# HUM-ASM-001.net
KiCad netlist of a schematic drawn in EAGLE
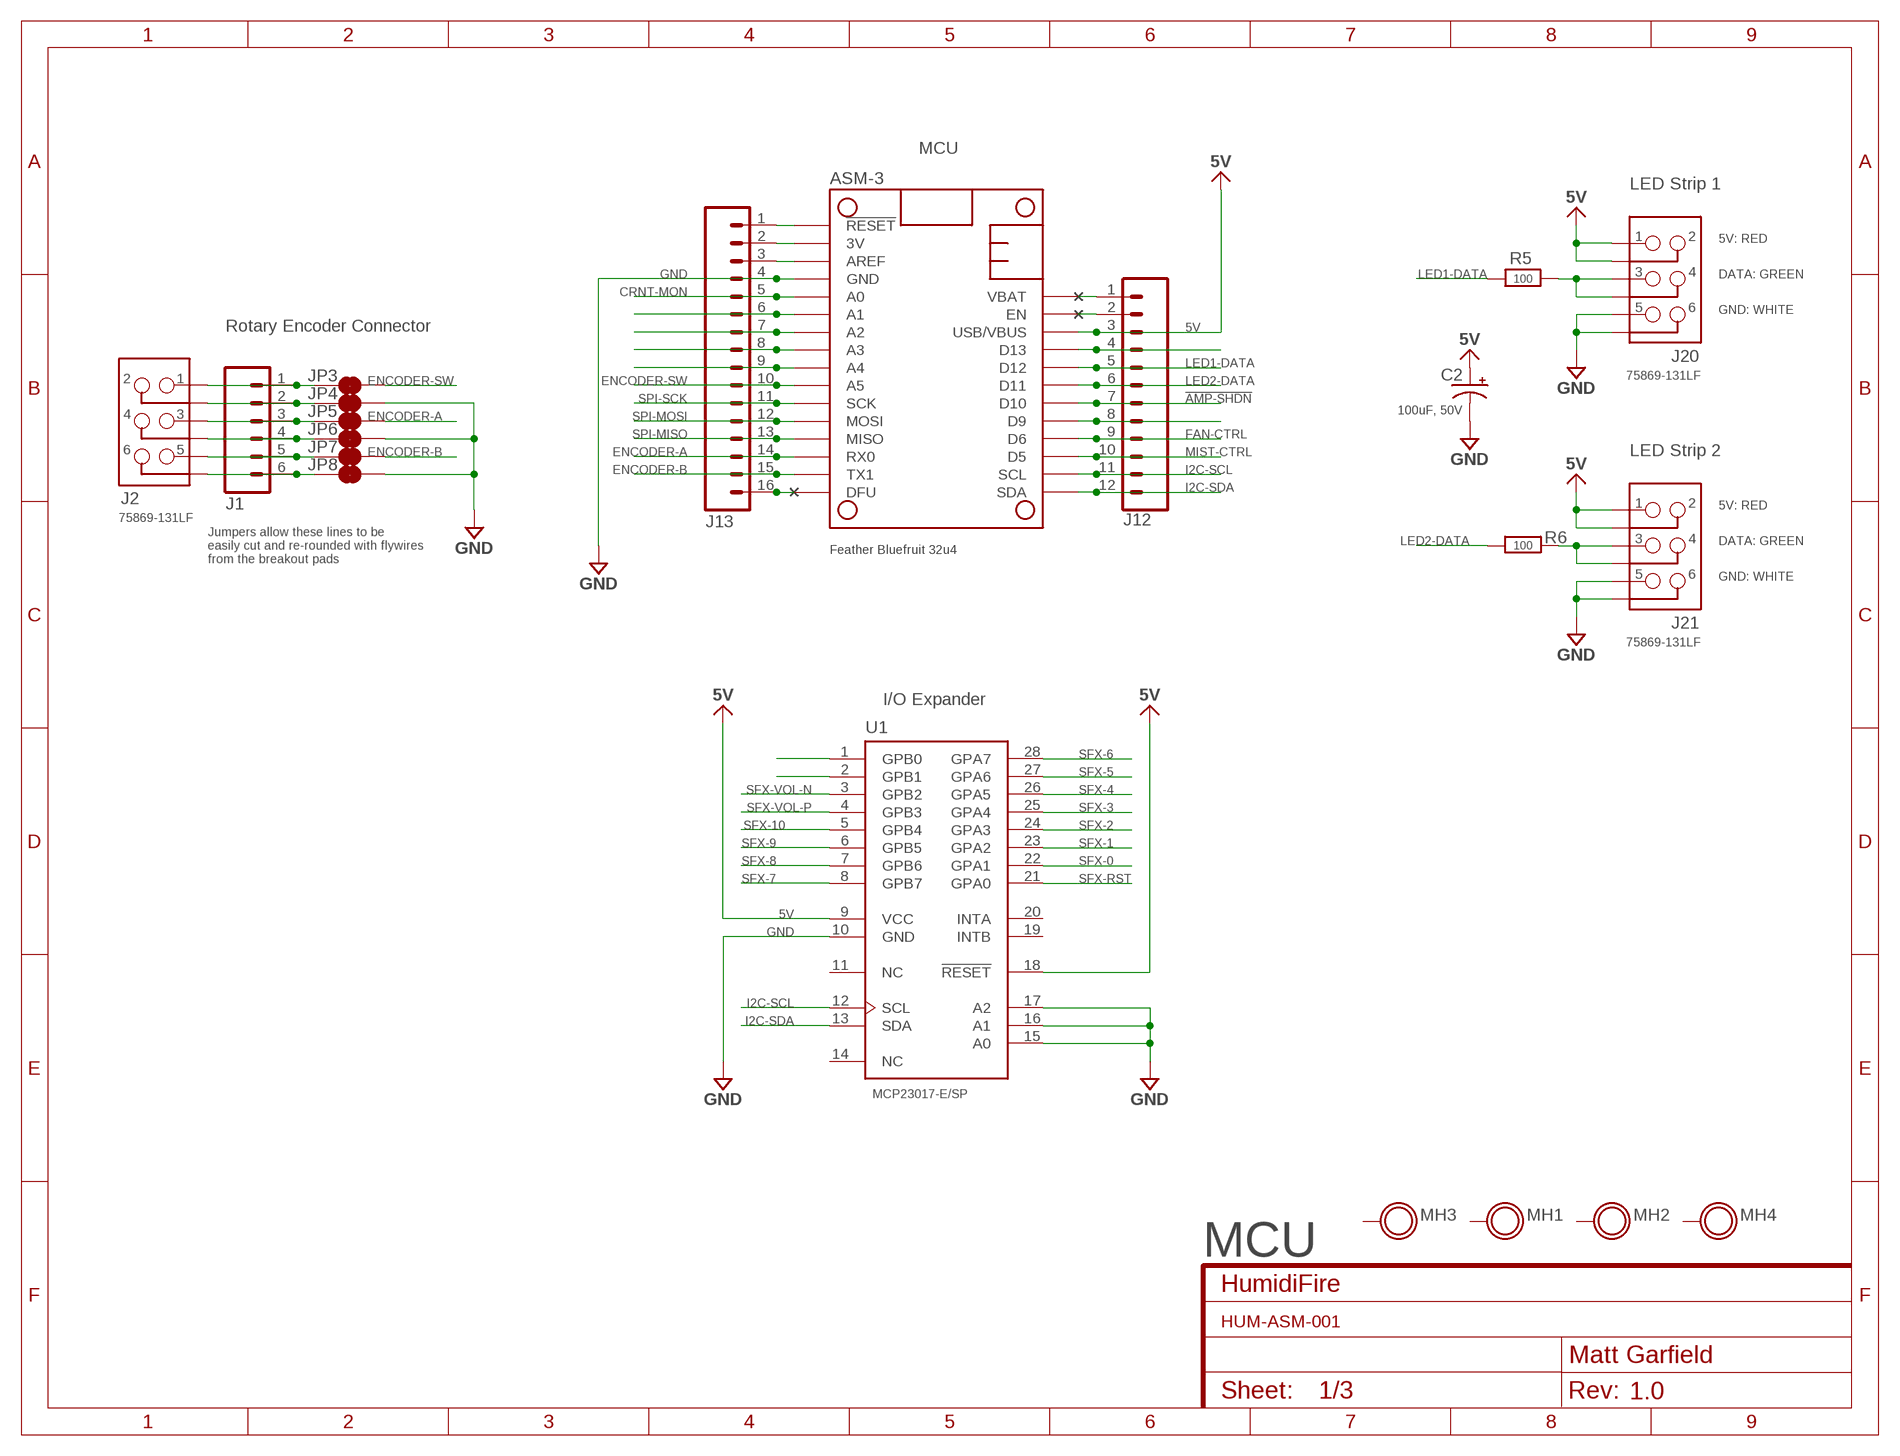
[diagram p0: schematic, sheet 1]
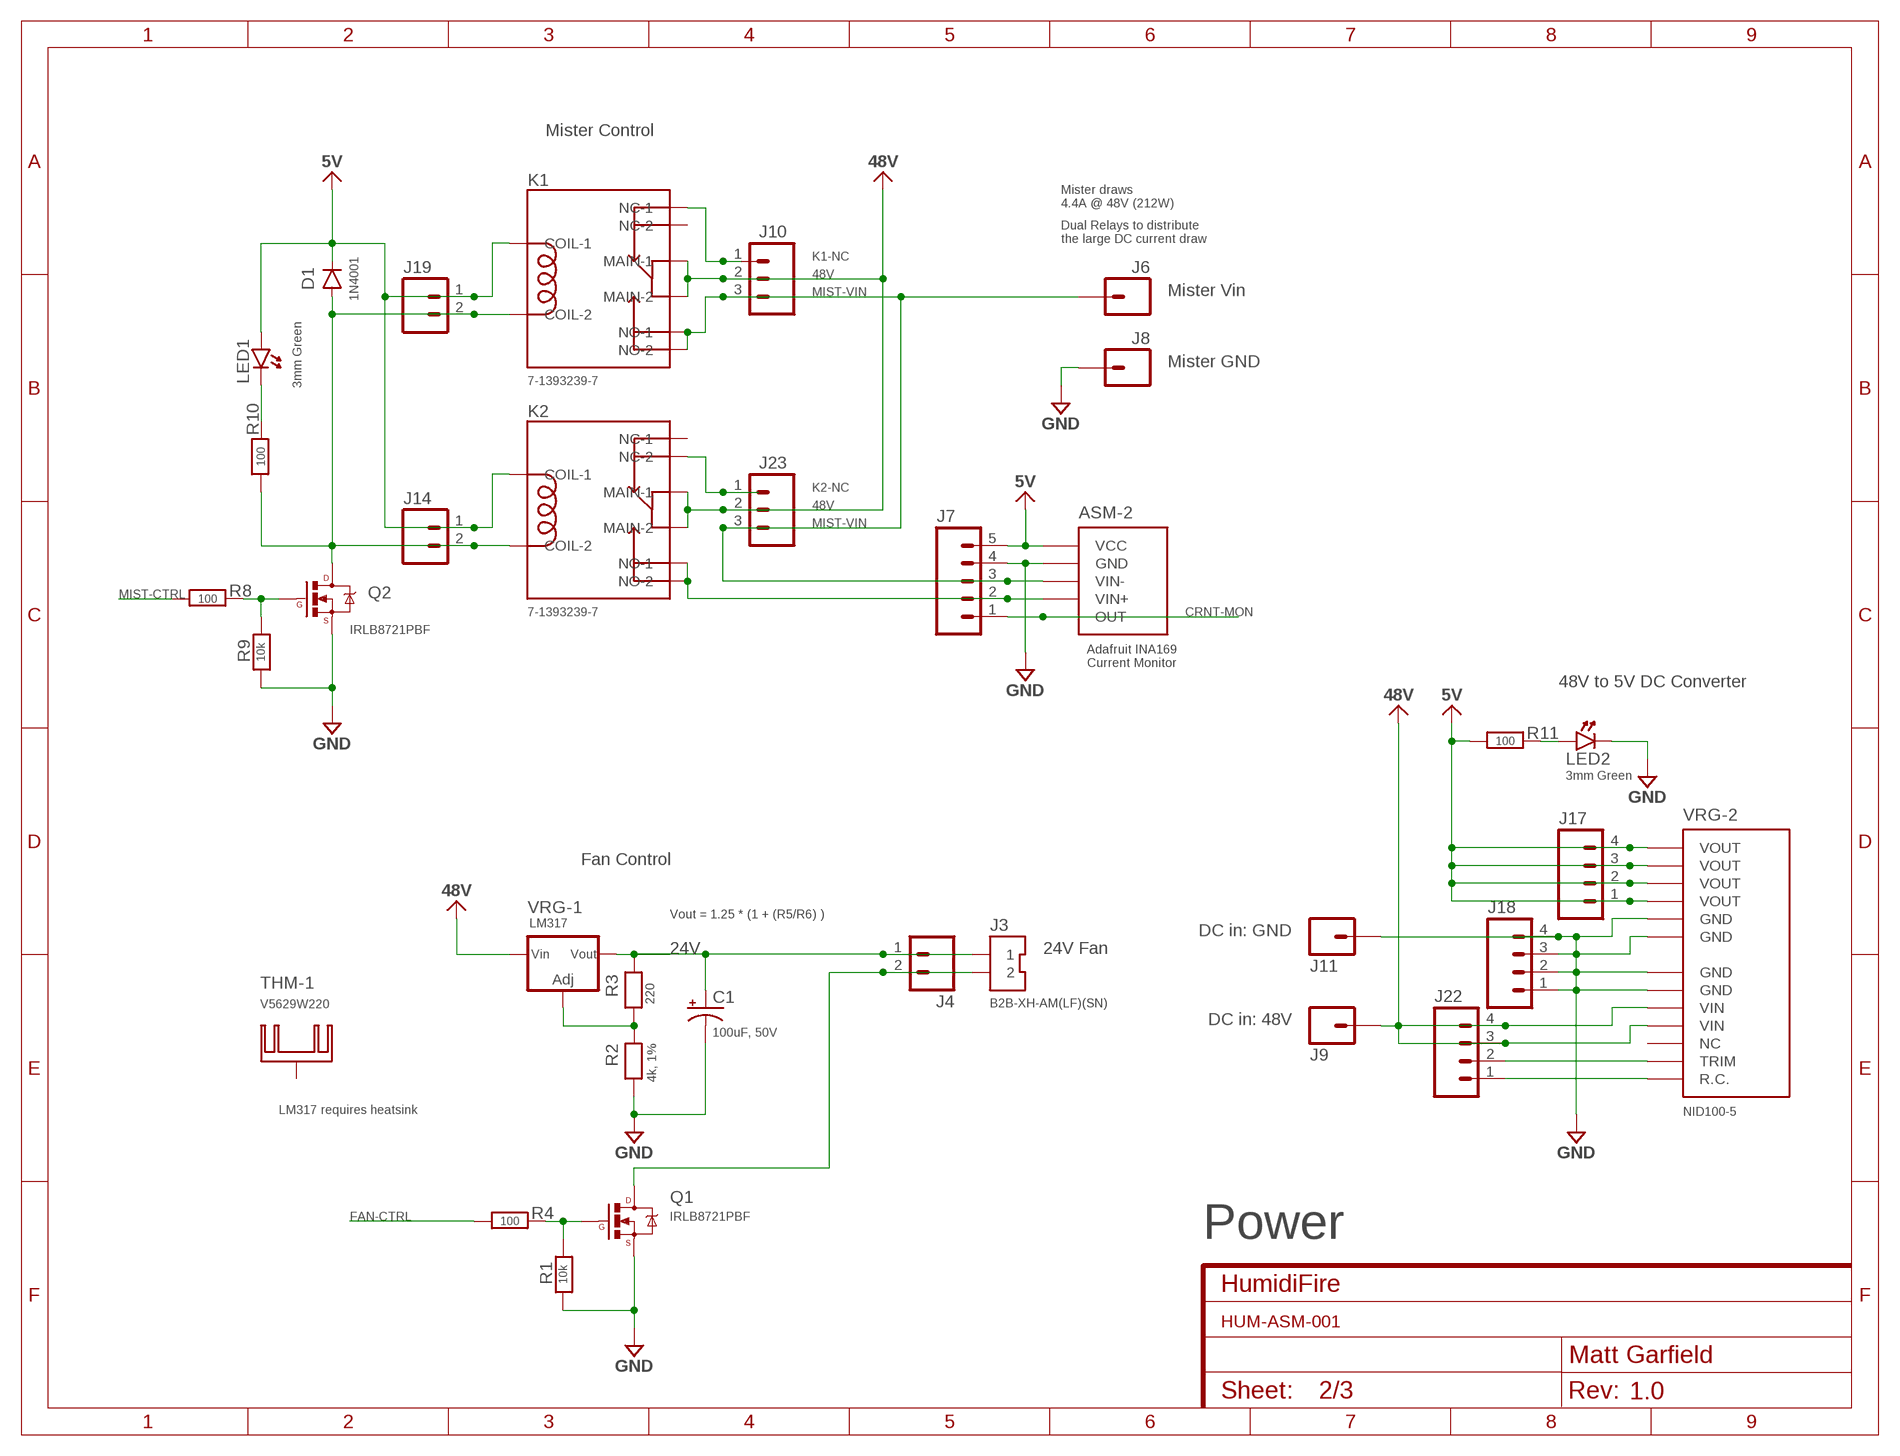
[diagram p1: schematic, sheet 2]
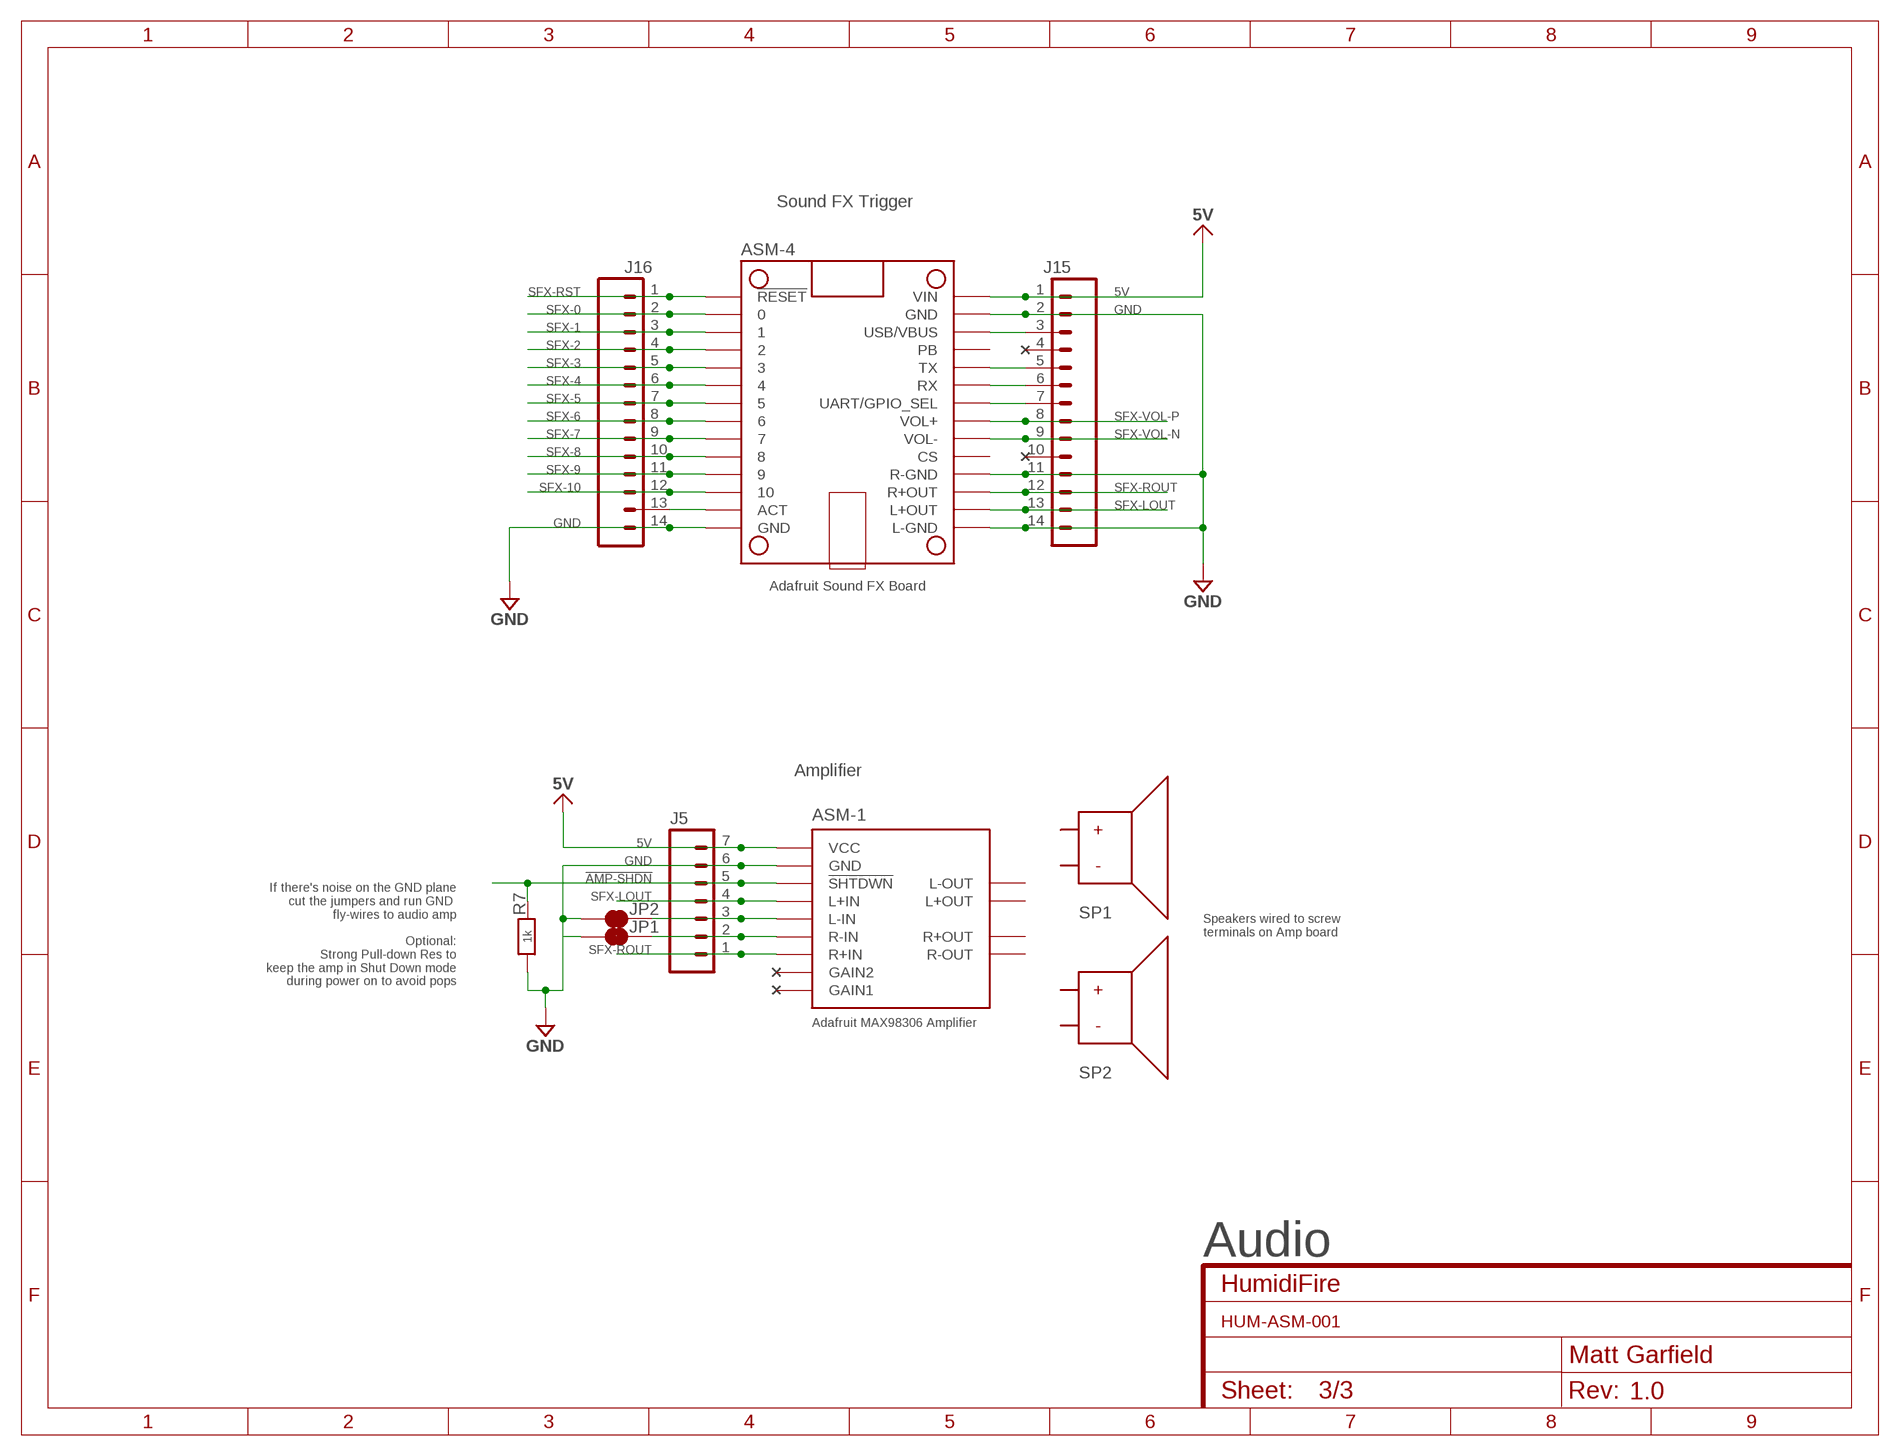
[diagram p2: schematic, sheet 3]

(export (version "E")
  (design (tool "Eeschema 10.0.6"))
  (components
    (comp (ref "ASM-1")
      (value "ASM_ADAFRUIT_MAX98306_AMP")
      (footprint "eagle-import:ASM_ADAFRUIT_MAX98306_AMP_MOUNTING_HOLES")
      (libsource (lib "eagle-import") (part "ASM_ADAFRUIT_MAX98306_AMP"))
    )
    (comp (ref "ASM-4")
      (value "ASM_ADAFRUIT_SOUND_FX_BOARD")
      (footprint "eagle-import:ASM_ADAFRUIT_SOUND_FX_BOARD")
      (libsource (lib "eagle-import") (part "ASM_ADAFRUIT_SOUND_FX_BOARD"))
    )
    (comp (ref "J5")
      (value "CON_HEADER_1X7NO_SILK")
      (footprint "eagle-import:1X07_NO_SILK")
      (libsource (lib "eagle-import") (part "CON_HEADER_1X7NO_SILK"))
    )
    (comp (ref "J15")
      (value "CON_HEADER_1X14")
      (footprint "eagle-import:1X14_NO_SILK")
      (libsource (lib "eagle-import") (part "CON_HEADER_1X14"))
    )
    (comp (ref "J16")
      (value "CON_HEADER_1X14")
      (footprint "eagle-import:1X14_NO_SILK")
      (libsource (lib "eagle-import") (part "CON_HEADER_1X14"))
    )
    (comp (ref "JP1")
      (value "CON_JUMPER_PAD-2-NC_BY_TRACE")
      (footprint "eagle-import:PAD-JUMPER-2-NC_BY_TRACE_YES_SILK")
      (libsource (lib "eagle-import") (part "CON_JUMPER_PAD-2-NC_BY_TRACE"))
    )
    (comp (ref "JP2")
      (value "CON_JUMPER_PAD-2-NC_BY_TRACE")
      (footprint "eagle-import:PAD-JUMPER-2-NC_BY_TRACE_YES_SILK")
      (libsource (lib "eagle-import") (part "CON_JUMPER_PAD-2-NC_BY_TRACE"))
    )
    (comp (ref "R7")
      (value "1k")
      (footprint "eagle-import:AXIAL-0.4")
      (libsource (lib "eagle-import") (part "RES_RESISTOR-PTH-1/4W"))
    )
    (comp (ref "ASM-3")
      (value "Feather Bluefruit 32u4")
      (footprint "eagle-import:ASM_ADAFRUIT_FEATHER_BLUEFRUIT")
      (libsource (lib "eagle-import") (part "ASM_ADAFRUIT_FEATHER_BLUEFRUIT"))
    )
    (comp (ref "C2")
      (value "100uF, 50V")
      (footprint "eagle-import:CAP_E-035X080")
      (libsource (lib "eagle-import") (part "CAP_THT_POL-E-035X080MM"))
    )
    (comp (ref "J1")
      (value "CON_HEADER_1X6NO_SILK_FEMALE_PTH")
      (footprint "eagle-import:1X06_NO_SILK")
      (libsource (lib "eagle-import") (part "CON_HEADER_1X6NO_SILK_FEMALE_PTH"))
    )
    (comp (ref "J2")
      (value "75869-131LF")
      (footprint "eagle-import:2X3-SHROUDED")
      (libsource (lib "eagle-import") (part "CON_HEADER_2X3-SHROUD"))
    )
    (comp (ref "J12")
      (value "CON_HEADER_1X12_NO_SILK")
      (footprint "eagle-import:1X12_NO_SILK")
      (libsource (lib "eagle-import") (part "CON_HEADER_1X12_NO_SILK"))
    )
    (comp (ref "J13")
      (value "CON_HEADER_1X16-1X16_NO_SILK")
      (footprint "eagle-import:1X16_NO_SILK")
      (libsource (lib "eagle-import") (part "CON_HEADER_1X16-1X16_NO_SILK"))
    )
    (comp (ref "J20")
      (value "75869-131LF")
      (footprint "eagle-import:2X3-SHROUDED")
      (libsource (lib "eagle-import") (part "CON_HEADER_2X3-SHROUD"))
    )
    (comp (ref "J21")
      (value "75869-131LF")
      (footprint "eagle-import:2X3-SHROUDED")
      (libsource (lib "eagle-import") (part "CON_HEADER_2X3-SHROUD"))
    )
    (comp (ref "JP3")
      (value "CON_JUMPER_PAD-2-NC_BY_TRACE")
      (footprint "eagle-import:PAD-JUMPER-2-NC_BY_TRACE_YES_SILK")
      (libsource (lib "eagle-import") (part "CON_JUMPER_PAD-2-NC_BY_TRACE"))
    )
    (comp (ref "JP4")
      (value "CON_JUMPER_PAD-2-NC_BY_TRACE")
      (footprint "eagle-import:PAD-JUMPER-2-NC_BY_TRACE_YES_SILK")
      (libsource (lib "eagle-import") (part "CON_JUMPER_PAD-2-NC_BY_TRACE"))
    )
    (comp (ref "JP5")
      (value "CON_JUMPER_PAD-2-NC_BY_TRACE")
      (footprint "eagle-import:PAD-JUMPER-2-NC_BY_TRACE_YES_SILK")
      (libsource (lib "eagle-import") (part "CON_JUMPER_PAD-2-NC_BY_TRACE"))
    )
    (comp (ref "JP6")
      (value "CON_JUMPER_PAD-2-NC_BY_TRACE")
      (footprint "eagle-import:PAD-JUMPER-2-NC_BY_TRACE_YES_SILK")
      (libsource (lib "eagle-import") (part "CON_JUMPER_PAD-2-NC_BY_TRACE"))
    )
    (comp (ref "JP7")
      (value "CON_JUMPER_PAD-2-NC_BY_TRACE")
      (footprint "eagle-import:PAD-JUMPER-2-NC_BY_TRACE_YES_SILK")
      (libsource (lib "eagle-import") (part "CON_JUMPER_PAD-2-NC_BY_TRACE"))
    )
    (comp (ref "JP8")
      (value "CON_JUMPER_PAD-2-NC_BY_TRACE")
      (footprint "eagle-import:PAD-JUMPER-2-NC_BY_TRACE_YES_SILK")
      (libsource (lib "eagle-import") (part "CON_JUMPER_PAD-2-NC_BY_TRACE"))
    )
    (comp (ref "MH1")
      (value "PCB_MOUNTING-HOLE_IN_PLATED")
      (footprint "eagle-import:TOOLING_HOLE_0.125_IN_HORSESHOE")
      (libsource (lib "eagle-import") (part "PCB_MOUNTING-HOLE_IN_PLATED"))
    )
    (comp (ref "MH2")
      (value "PCB_MOUNTING-HOLE_IN_PLATED")
      (footprint "eagle-import:TOOLING_HOLE_0.125_IN_HORSESHOE")
      (libsource (lib "eagle-import") (part "PCB_MOUNTING-HOLE_IN_PLATED"))
    )
    (comp (ref "MH3")
      (value "PCB_MOUNTING-HOLE_IN_PLATED")
      (footprint "eagle-import:TOOLING_HOLE_0.125_IN_HORSESHOE")
      (libsource (lib "eagle-import") (part "PCB_MOUNTING-HOLE_IN_PLATED"))
    )
    (comp (ref "MH4")
      (value "PCB_MOUNTING-HOLE_IN_PLATED")
      (footprint "eagle-import:TOOLING_HOLE_0.125_IN_HORSESHOE")
      (libsource (lib "eagle-import") (part "PCB_MOUNTING-HOLE_IN_PLATED"))
    )
    (comp (ref "R5")
      (value "100")
      (footprint "eagle-import:AXIAL-0.4")
      (libsource (lib "eagle-import") (part "RES_RESISTOR-PTH-1/4W"))
    )
    (comp (ref "R6")
      (value "100")
      (footprint "eagle-import:AXIAL-0.4")
      (libsource (lib "eagle-import") (part "RES_RESISTOR-PTH-1/4W"))
    )
    (comp (ref "U1")
      (value "MCP23017-E/SP")
      (footprint "eagle-import:DIP787W45P254L3556H508Q28")
      (fields (field (name "DIGI-KEY_PART_NUMBER") "MCP23017-E/SP-ND") (field (name "MF") "Microchip"))
      (libsource (lib "eagle-import") (part "IIC_MCP23017-E/SP"))
    )
    (comp (ref "ASM-2")
      (value "ASM_ADAFRUIT_INA169")
      (footprint "eagle-import:ASM_ADAFRUIT_INA169_MOUNTING_HOLES")
      (libsource (lib "eagle-import") (part "ASM_ADAFRUIT_INA169"))
    )
    (comp (ref "C1")
      (value "100uF, 50V")
      (footprint "eagle-import:CAP_E-035X080")
      (libsource (lib "eagle-import") (part "CAP_THT_POL-E-035X080MM"))
    )
    (comp (ref "D1")
      (value "1N4001")
      (footprint "eagle-import:DIODE-1N4001")
      (libsource (lib "eagle-import") (part "DIO_DIODEPTH"))
    )
    (comp (ref "J3")
      (value "B2B-XH-AM(LF)(SN)")
      (footprint "eagle-import:JST-2-PTH-VERT_XH")
      (libsource (lib "eagle-import") (part "CON_JST_2-PIN_B2B-XH-AM"))
    )
    (comp (ref "J4")
      (value "CON_HEADER_1X21X02_NO_SILK")
      (footprint "eagle-import:1X02_NO_SILK")
      (libsource (lib "eagle-import") (part "CON_HEADER_1X21X02_NO_SILK"))
    )
    (comp (ref "J6")
      (value "CON_HEADER_1X1-QC_TAB_121786-1")
      (footprint "eagle-import:TE_1217861-1")
      (libsource (lib "eagle-import") (part "CON_HEADER_1X1-QC_TAB_121786-1"))
    )
    (comp (ref "J7")
      (value "CON_HEADER_1X5NO_SILK")
      (footprint "eagle-import:1X05_NO_SILK")
      (libsource (lib "eagle-import") (part "CON_HEADER_1X5NO_SILK"))
    )
    (comp (ref "J8")
      (value "CON_HEADER_1X1-QC_TAB_121786-1")
      (footprint "eagle-import:TE_1217861-1")
      (libsource (lib "eagle-import") (part "CON_HEADER_1X1-QC_TAB_121786-1"))
    )
    (comp (ref "J9")
      (value "CON_HEADER_1X1-QC_TAB_121786-1")
      (footprint "eagle-import:TE_1217861-1")
      (libsource (lib "eagle-import") (part "CON_HEADER_1X1-QC_TAB_121786-1"))
    )
    (comp (ref "J10")
      (value "CON_HEADER_1X3PTH")
      (footprint "eagle-import:1X03")
      (libsource (lib "eagle-import") (part "CON_HEADER_1X3PTH"))
    )
    (comp (ref "J11")
      (value "CON_HEADER_1X1-QC_TAB_121786-1")
      (footprint "eagle-import:TE_1217861-1")
      (libsource (lib "eagle-import") (part "CON_HEADER_1X1-QC_TAB_121786-1"))
    )
    (comp (ref "J14")
      (value "CON_HEADER_1X21X02_NO_SILK")
      (footprint "eagle-import:1X02_NO_SILK")
      (libsource (lib "eagle-import") (part "CON_HEADER_1X21X02_NO_SILK"))
    )
    (comp (ref "J17")
      (value "CON_HEADER_1X4PTH")
      (footprint "eagle-import:1X04")
      (libsource (lib "eagle-import") (part "CON_HEADER_1X4PTH"))
    )
    (comp (ref "J18")
      (value "CON_HEADER_1X4PTH")
      (footprint "eagle-import:1X04")
      (libsource (lib "eagle-import") (part "CON_HEADER_1X4PTH"))
    )
    (comp (ref "J19")
      (value "CON_HEADER_1X21X02_NO_SILK")
      (footprint "eagle-import:1X02_NO_SILK")
      (libsource (lib "eagle-import") (part "CON_HEADER_1X21X02_NO_SILK"))
    )
    (comp (ref "J22")
      (value "CON_HEADER_1X4NO_SILK_ALL_ROUND")
      (footprint "eagle-import:1X04_NO_SILK_ALL_ROUND")
      (libsource (lib "eagle-import") (part "CON_HEADER_1X4NO_SILK_ALL_ROUND"))
    )
    (comp (ref "J23")
      (value "CON_HEADER_1X3PTH")
      (footprint "eagle-import:1X03")
      (libsource (lib "eagle-import") (part "CON_HEADER_1X3PTH"))
    )
    (comp (ref "K1")
      (value "7-1393239-7")
      (footprint "eagle-import:RELAY_TE_7-1393239-7")
      (libsource (lib "eagle-import") (part "EMD_RELAY_SPDT_8-PIN_TE_7-1393239-7"))
    )
    (comp (ref "K2")
      (value "7-1393239-7")
      (footprint "eagle-import:RELAY_TE_7-1393239-7")
      (libsource (lib "eagle-import") (part "EMD_RELAY_SPDT_8-PIN_TE_7-1393239-7"))
    )
    (comp (ref "LED1")
      (value "3mm Green")
      (footprint "eagle-import:LED3MM")
      (libsource (lib "eagle-import") (part "LED_THT-3MM"))
    )
    (comp (ref "LED2")
      (value "3mm Green")
      (footprint "eagle-import:LED3MM")
      (libsource (lib "eagle-import") (part "LED_THT-3MM"))
    )
    (comp (ref "Q1")
      (value "IRLB8721PBF")
      (footprint "eagle-import:TO-220-VERTICAL")
      (libsource (lib "eagle-import") (part "TRN_MOSFET-N_TO-220_VERTICAL"))
    )
    (comp (ref "Q2")
      (value "IRLB8721PBF")
      (footprint "eagle-import:TO-220-VERTICAL")
      (libsource (lib "eagle-import") (part "TRN_MOSFET-N_TO-220_VERTICAL"))
    )
    (comp (ref "R1")
      (value "10k")
      (footprint "eagle-import:AXIAL-0.4")
      (libsource (lib "eagle-import") (part "RES_RESISTOR-PTH-1/4W"))
    )
    (comp (ref "R2")
      (value "4k, 1%")
      (footprint "eagle-import:AXIAL-0.4")
      (libsource (lib "eagle-import") (part "RES_RESISTOR-PTH-1/4W"))
    )
    (comp (ref "R3")
      (value "220")
      (footprint "eagle-import:AXIAL-0.4")
      (libsource (lib "eagle-import") (part "RES_RESISTOR-PTH-1/4W"))
    )
    (comp (ref "R4")
      (value "100")
      (footprint "eagle-import:AXIAL-0.4")
      (libsource (lib "eagle-import") (part "RES_RESISTOR-PTH-1/4W"))
    )
    (comp (ref "R8")
      (value "100")
      (footprint "eagle-import:AXIAL-0.4")
      (libsource (lib "eagle-import") (part "RES_RESISTOR-PTH-1/4W"))
    )
    (comp (ref "R9")
      (value "10k")
      (footprint "eagle-import:AXIAL-0.4")
      (libsource (lib "eagle-import") (part "RES_RESISTOR-PTH-1/4W"))
    )
    (comp (ref "R10")
      (value "100")
      (footprint "eagle-import:AXIAL-0.4")
      (libsource (lib "eagle-import") (part "RES_RESISTOR-PTH-1/4W"))
    )
    (comp (ref "R11")
      (value "100")
      (footprint "eagle-import:AXIAL-0.4")
      (libsource (lib "eagle-import") (part "RES_RESISTOR-PTH-1/4W"))
    )
    (comp (ref "THM-1")
      (value "V5629W220")
      (footprint "eagle-import:SK95-2M3")
      (libsource (lib "eagle-import") (part "THM_HEATSINK_1-PIN"))
    )
    (comp (ref "VRG-1")
      (value "LM317")
      (footprint "eagle-import:TO-220-VERTICAL")
      (libsource (lib "eagle-import") (part "VRG_LM317_TO-220_VERTICAL"))
    )
    (comp (ref "VRG-2")
      (value "NID100-5")
      (footprint "eagle-import:VRG_NID100-X")
      (libsource (lib "eagle-import") (part "VRG_NID100"))
    )
  )
  (nets
    (net (code "1") (name "5V") (class "Default")
      (node (ref "ASM-1") (pin "1") (pinfunction "VCC_1") (pintype "power_in"))
      (node (ref "ASM-2") (pin "1") (pinfunction "VCC_1") (pintype "power_in"))
      (node (ref "ASM-3") (pin "USB/VBUS") (pinfunction "USB/VBUS_USB/VBUS") (pintype "power_in"))
      (node (ref "ASM-4") (pin "28") (pinfunction "VIN_28") (pintype "power_in"))
      (node (ref "C2") (pin "+") (pinfunction "+_+") (pintype "passive"))
      (node (ref "D1") (pin "C") (pinfunction "C_C") (pintype "passive"))
      (node (ref "J12") (pin "3") (pinfunction "3_3") (pintype "passive"))
      (node (ref "J14") (pin "1") (pinfunction "P1_1") (pintype "passive"))
      (node (ref "J15") (pin "1") (pinfunction "1_1") (pintype "passive"))
      (node (ref "J17") (pin "1") (pinfunction "1_1") (pintype "passive"))
      (node (ref "J17") (pin "2") (pinfunction "2_2") (pintype "passive"))
      (node (ref "J17") (pin "3") (pinfunction "3_3") (pintype "passive"))
      (node (ref "J17") (pin "4") (pinfunction "4_4") (pintype "passive"))
      (node (ref "J19") (pin "1") (pinfunction "P1_1") (pintype "passive"))
      (node (ref "J20") (pin "1") (pinfunction "1_1") (pintype "bidirectional"))
      (node (ref "J20") (pin "2") (pinfunction "2_2") (pintype "bidirectional"))
      (node (ref "J21") (pin "1") (pinfunction "1_1") (pintype "bidirectional"))
      (node (ref "J21") (pin "2") (pinfunction "2_2") (pintype "bidirectional"))
      (node (ref "J5") (pin "7") (pinfunction "7_7") (pintype "passive"))
      (node (ref "J7") (pin "5") (pinfunction "5_5") (pintype "passive"))
      (node (ref "K1") (pin "COIL-1") (pinfunction "COIL-1_COIL-1") (pintype "bidirectional"))
      (node (ref "K2") (pin "COIL-1") (pinfunction "COIL-1_COIL-1") (pintype "bidirectional"))
      (node (ref "LED1") (pin "A") (pinfunction "A_A") (pintype "passive"))
      (node (ref "R11") (pin "P$1") (pinfunction "P1_P$1") (pintype "passive"))
      (node (ref "U1") (pin "18") (pinfunction "~{RESET}_18") (pintype "input"))
      (node (ref "U1") (pin "9") (pinfunction "VCC_9") (pintype "power_in"))
      (node (ref "VRG-2") (pin "P$1") (pinfunction "VOUT_P$1") (pintype "power_in"))
      (node (ref "VRG-2") (pin "P$2") (pinfunction "VOUT_P$2") (pintype "power_in"))
      (node (ref "VRG-2") (pin "P$3") (pinfunction "VOUT_P$3") (pintype "power_in"))
      (node (ref "VRG-2") (pin "P$4") (pinfunction "VOUT_P$4") (pintype "power_in"))
    )
    (net (code "2") (name "24V") (class "Default")
      (node (ref "C1") (pin "+") (pinfunction "+_+") (pintype "passive"))
      (node (ref "J3") (pin "1") (pinfunction "1_1") (pintype "bidirectional"))
      (node (ref "J4") (pin "1") (pinfunction "P1_1") (pintype "passive"))
      (node (ref "R3") (pin "P$2") (pinfunction "P2_P$2") (pintype "passive"))
      (node (ref "VRG-1") (pin "P2") (pinfunction "VOUT_P2") (pintype "power_in"))
    )
    (net (code "3") (name "48V") (class "Default")
      (node (ref "J10") (pin "2") (pinfunction "P2_2") (pintype "passive"))
      (node (ref "J22") (pin "3") (pinfunction "3_3") (pintype "passive"))
      (node (ref "J22") (pin "4") (pinfunction "4_4") (pintype "passive"))
      (node (ref "J23") (pin "2") (pinfunction "P2_2") (pintype "passive"))
      (node (ref "J9") (pin "1") (pinfunction "1_1") (pintype "passive"))
      (node (ref "J9") (pin "2") (pinfunction "1_2") (pintype "passive"))
      (node (ref "K1") (pin "MAIN-1") (pinfunction "MAIN-1_MAIN-1") (pintype "bidirectional"))
      (node (ref "K1") (pin "MAIN-2") (pinfunction "MAIN-2_MAIN-2") (pintype "bidirectional"))
      (node (ref "K2") (pin "MAIN-1") (pinfunction "MAIN-1_MAIN-1") (pintype "bidirectional"))
      (node (ref "K2") (pin "MAIN-2") (pinfunction "MAIN-2_MAIN-2") (pintype "bidirectional"))
      (node (ref "VRG-1") (pin "P3") (pinfunction "VIN_P3") (pintype "power_in"))
      (node (ref "VRG-2") (pin "P$10") (pinfunction "VIN_P$10") (pintype "power_in"))
      (node (ref "VRG-2") (pin "P$9") (pinfunction "VIN_P$9") (pintype "power_in"))
    )
    (net (code "4") (name "CRNT-MON") (class "Default")
      (node (ref "ASM-2") (pin "5") (pinfunction "OUT_5") (pintype "output"))
      (node (ref "ASM-3") (pin "A0") (pinfunction "A0_A0") (pintype "bidirectional"))
      (node (ref "J13") (pin "5") (pinfunction "5_5") (pintype "passive"))
      (node (ref "J7") (pin "1") (pinfunction "1_1") (pintype "passive"))
    )
    (net (code "5") (name "ENCODER-A") (class "Default")
      (node (ref "ASM-3") (pin "RX0") (pinfunction "RX0_RX0") (pintype "bidirectional"))
      (node (ref "J13") (pin "14") (pinfunction "14_14") (pintype "passive"))
      (node (ref "JP5") (pin "1") (pinfunction "1_1") (pintype "passive"))
    )
    (net (code "6") (name "ENCODER-B") (class "Default")
      (node (ref "ASM-3") (pin "TX1") (pinfunction "TX1_TX1") (pintype "bidirectional"))
      (node (ref "J13") (pin "15") (pinfunction "15_15") (pintype "passive"))
      (node (ref "JP7") (pin "1") (pinfunction "1_1") (pintype "passive"))
    )
    (net (code "7") (name "ENCODER-SW") (class "Default")
      (node (ref "ASM-3") (pin "A5") (pinfunction "A5_A5") (pintype "bidirectional"))
      (node (ref "J13") (pin "10") (pinfunction "10_10") (pintype "passive"))
      (node (ref "JP3") (pin "1") (pinfunction "1_1") (pintype "passive"))
    )
    (net (code "8") (name "FAN-CTRL") (class "Default")
      (node (ref "ASM-3") (pin "D6") (pinfunction "D6_D6") (pintype "bidirectional"))
      (node (ref "J12") (pin "9") (pinfunction "9_9") (pintype "passive"))
      (node (ref "R4") (pin "P$1") (pinfunction "P1_P$1") (pintype "passive"))
    )
    (net (code "9") (name "GND") (class "Default")
      (node (ref "ASM-1") (pin "2") (pinfunction "GND_2") (pintype "power_in"))
      (node (ref "ASM-2") (pin "2") (pinfunction "GND_2") (pintype "power_in"))
      (node (ref "ASM-3") (pin "GND@4") (pinfunction "GND_GND@4") (pintype "power_in"))
      (node (ref "ASM-4") (pin "14") (pinfunction "GND_14") (pintype "power_in"))
      (node (ref "ASM-4") (pin "15") (pinfunction "L-GND_15") (pintype "power_in"))
      (node (ref "ASM-4") (pin "18") (pinfunction "R-GND_18") (pintype "bidirectional"))
      (node (ref "ASM-4") (pin "27") (pinfunction "GND_27") (pintype "power_in"))
      (node (ref "C1") (pin "-") (pinfunction "-_-") (pintype "passive"))
      (node (ref "C2") (pin "-") (pinfunction "-_-") (pintype "passive"))
      (node (ref "J11") (pin "1") (pinfunction "1_1") (pintype "passive"))
      (node (ref "J11") (pin "2") (pinfunction "1_2") (pintype "passive"))
      (node (ref "J13") (pin "4") (pinfunction "4_4") (pintype "passive"))
      (node (ref "J15") (pin "11") (pinfunction "11_11") (pintype "passive"))
      (node (ref "J15") (pin "14") (pinfunction "14_14") (pintype "passive"))
      (node (ref "J15") (pin "2") (pinfunction "2_2") (pintype "passive"))
      (node (ref "J16") (pin "14") (pinfunction "14_14") (pintype "passive"))
      (node (ref "J18") (pin "1") (pinfunction "1_1") (pintype "passive"))
      (node (ref "J18") (pin "2") (pinfunction "2_2") (pintype "passive"))
      (node (ref "J18") (pin "3") (pinfunction "3_3") (pintype "passive"))
      (node (ref "J18") (pin "4") (pinfunction "4_4") (pintype "passive"))
      (node (ref "J20") (pin "5") (pinfunction "5_5") (pintype "bidirectional"))
      (node (ref "J20") (pin "6") (pinfunction "6_6") (pintype "bidirectional"))
      (node (ref "J21") (pin "5") (pinfunction "5_5") (pintype "bidirectional"))
      (node (ref "J21") (pin "6") (pinfunction "6_6") (pintype "bidirectional"))
      (node (ref "J5") (pin "6") (pinfunction "6_6") (pintype "passive"))
      (node (ref "J7") (pin "4") (pinfunction "4_4") (pintype "passive"))
      (node (ref "J8") (pin "1") (pinfunction "1_1") (pintype "passive"))
      (node (ref "J8") (pin "2") (pinfunction "1_2") (pintype "passive"))
      (node (ref "JP1") (pin "1") (pinfunction "1_1") (pintype "passive"))
      (node (ref "JP2") (pin "1") (pinfunction "1_1") (pintype "passive"))
      (node (ref "JP4") (pin "1") (pinfunction "1_1") (pintype "passive"))
      (node (ref "JP6") (pin "1") (pinfunction "1_1") (pintype "passive"))
      (node (ref "JP8") (pin "1") (pinfunction "1_1") (pintype "passive"))
      (node (ref "LED2") (pin "K") (pinfunction "C_K") (pintype "passive"))
      (node (ref "Q1") (pin "P3") (pinfunction "S_P3") (pintype "passive"))
      (node (ref "Q2") (pin "P3") (pinfunction "S_P3") (pintype "passive"))
      (node (ref "R1") (pin "P$2") (pinfunction "P2_P$2") (pintype "passive"))
      (node (ref "R2") (pin "P$1") (pinfunction "P1_P$1") (pintype "passive"))
      (node (ref "R7") (pin "P$1") (pinfunction "P1_P$1") (pintype "passive"))
      (node (ref "R9") (pin "P$2") (pinfunction "P2_P$2") (pintype "passive"))
      (node (ref "U1") (pin "10") (pinfunction "GND_10") (pintype "power_in"))
      (node (ref "U1") (pin "15") (pinfunction "A0_15") (pintype "input"))
      (node (ref "U1") (pin "16") (pinfunction "A1_16") (pintype "input"))
      (node (ref "U1") (pin "17") (pinfunction "A2_17") (pintype "input"))
      (node (ref "VRG-2") (pin "P$5") (pinfunction "GND_P$5") (pintype "power_in"))
      (node (ref "VRG-2") (pin "P$6") (pinfunction "GND_P$6") (pintype "power_in"))
      (node (ref "VRG-2") (pin "P$7") (pinfunction "GND_P$7") (pintype "power_in"))
      (node (ref "VRG-2") (pin "P$8") (pinfunction "GND_P$8") (pintype "power_in"))
    )
    (net (code "10") (name "I2C-SCL") (class "Default")
      (node (ref "ASM-3") (pin "SCL") (pinfunction "SCL_SCL") (pintype "bidirectional"))
      (node (ref "J12") (pin "11") (pinfunction "11_11") (pintype "passive"))
      (node (ref "U1") (pin "12") (pinfunction "SCL_12") (pintype "input"))
    )
    (net (code "11") (name "I2C-SDA") (class "Default")
      (node (ref "ASM-3") (pin "SDA") (pinfunction "SDA_SDA") (pintype "bidirectional"))
      (node (ref "J12") (pin "12") (pinfunction "12_12") (pintype "passive"))
      (node (ref "U1") (pin "13") (pinfunction "SDA_13") (pintype "bidirectional"))
    )
    (net (code "12") (name "K1-NC") (class "Default")
      (node (ref "J10") (pin "1") (pinfunction "P1_1") (pintype "passive"))
      (node (ref "K1") (pin "NC-1") (pinfunction "NC-1_NC-1") (pintype "bidirectional"))
    )
    (net (code "13") (name "K2-NC") (class "Default")
      (node (ref "J23") (pin "1") (pinfunction "P1_1") (pintype "passive"))
      (node (ref "K2") (pin "NC-2") (pinfunction "NC-2_NC-2") (pintype "bidirectional"))
    )
    (net (code "14") (name "LED1-DATA") (class "Default")
      (node (ref "ASM-3") (pin "D12") (pinfunction "D12_D12") (pintype "bidirectional"))
      (node (ref "J12") (pin "5") (pinfunction "5_5") (pintype "passive"))
      (node (ref "R5") (pin "P$2") (pinfunction "P2_P$2") (pintype "passive"))
    )
    (net (code "15") (name "LED2-DATA") (class "Default")
      (node (ref "ASM-3") (pin "D11") (pinfunction "D11_D11") (pintype "bidirectional"))
      (node (ref "J12") (pin "6") (pinfunction "6_6") (pintype "passive"))
      (node (ref "R6") (pin "P$1") (pinfunction "P1_P$1") (pintype "passive"))
    )
    (net (code "16") (name "MIST-CTRL") (class "Default")
      (node (ref "ASM-3") (pin "D5") (pinfunction "D5_D5") (pintype "bidirectional"))
      (node (ref "J12") (pin "10") (pinfunction "10_10") (pintype "passive"))
      (node (ref "R8") (pin "P$1") (pinfunction "P1_P$1") (pintype "passive"))
    )
    (net (code "17") (name "MIST-VIN") (class "Default")
      (node (ref "ASM-2") (pin "3") (pinfunction "VIN-_3") (pintype "bidirectional"))
      (node (ref "J10") (pin "3") (pinfunction "P3_3") (pintype "passive"))
      (node (ref "J23") (pin "3") (pinfunction "P3_3") (pintype "passive"))
      (node (ref "J6") (pin "1") (pinfunction "1_1") (pintype "passive"))
      (node (ref "J6") (pin "2") (pinfunction "1_2") (pintype "passive"))
      (node (ref "J7") (pin "3") (pinfunction "3_3") (pintype "passive"))
      (node (ref "K1") (pin "NO-1") (pinfunction "NO-1_NO-1") (pintype "bidirectional"))
      (node (ref "K1") (pin "NO-2") (pinfunction "NO-2_NO-2") (pintype "bidirectional"))
    )
    (net (code "18") (name "Net-(ASM-1-L-IN)") (class "Default")
      (node (ref "ASM-1") (pin "5") (pinfunction "L-IN_5") (pintype "input"))
      (node (ref "J5") (pin "3") (pinfunction "3_3") (pintype "passive"))
      (node (ref "JP2") (pin "2") (pinfunction "2_2") (pintype "passive"))
    )
    (net (code "19") (name "Net-(ASM-1-R-IN)") (class "Default")
      (node (ref "ASM-1") (pin "6") (pinfunction "R-IN_6") (pintype "input"))
      (node (ref "J5") (pin "2") (pinfunction "2_2") (pintype "passive"))
      (node (ref "JP1") (pin "2") (pinfunction "2_2") (pintype "passive"))
    )
    (net (code "20") (name "Net-(ASM-2-VIN+)") (class "Default")
      (node (ref "ASM-2") (pin "4") (pinfunction "VIN+_4") (pintype "bidirectional"))
      (node (ref "J7") (pin "2") (pinfunction "2_2") (pintype "passive"))
      (node (ref "K2") (pin "NO-1") (pinfunction "NO-1_NO-1") (pintype "bidirectional"))
      (node (ref "K2") (pin "NO-2") (pinfunction "NO-2_NO-2") (pintype "bidirectional"))
    )
    (net (code "21") (name "Net-(ASM-3-3V)") (class "Default")
      (node (ref "ASM-3") (pin "3V3") (pinfunction "3V_3V3") (pintype "power_in"))
      (node (ref "J13") (pin "2") (pinfunction "2_2") (pintype "passive"))
    )
    (net (code "22") (name "Net-(ASM-3-PadA1)") (class "Default")
      (node (ref "ASM-3") (pin "A1") (pinfunction "A1_A1") (pintype "bidirectional"))
      (node (ref "J13") (pin "6") (pinfunction "6_6") (pintype "passive"))
    )
    (net (code "23") (name "Net-(ASM-3-PadA2)") (class "Default")
      (node (ref "ASM-3") (pin "A2") (pinfunction "A2_A2") (pintype "bidirectional"))
      (node (ref "J13") (pin "7") (pinfunction "7_7") (pintype "passive"))
    )
    (net (code "24") (name "Net-(ASM-3-PadA3)") (class "Default")
      (node (ref "ASM-3") (pin "A3") (pinfunction "A3_A3") (pintype "bidirectional"))
      (node (ref "J13") (pin "8") (pinfunction "8_8") (pintype "passive"))
    )
    (net (code "25") (name "Net-(ASM-3-PadA4)") (class "Default")
      (node (ref "ASM-3") (pin "A4") (pinfunction "A4_A4") (pintype "bidirectional"))
      (node (ref "J13") (pin "9") (pinfunction "9_9") (pintype "passive"))
    )
    (net (code "26") (name "Net-(ASM-3-PadAREF)") (class "Default")
      (node (ref "ASM-3") (pin "AREF") (pinfunction "AREF_AREF") (pintype "passive"))
      (node (ref "J13") (pin "3") (pinfunction "3_3") (pintype "passive"))
    )
    (net (code "27") (name "Net-(ASM-3-PadD9)") (class "Default")
      (node (ref "ASM-3") (pin "D9") (pinfunction "D9_D9") (pintype "bidirectional"))
      (node (ref "J12") (pin "8") (pinfunction "8_8") (pintype "passive"))
    )
    (net (code "28") (name "Net-(ASM-3-PadD13)") (class "Default")
      (node (ref "ASM-3") (pin "D13") (pinfunction "D13_D13") (pintype "bidirectional"))
      (node (ref "J12") (pin "4") (pinfunction "4_4") (pintype "passive"))
    )
    (net (code "29") (name "Net-(ASM-3-PadDFU)") (class "Default")
      (node (ref "ASM-3") (pin "DFU") (pinfunction "DFU_DFU") (pintype "bidirectional"))
      (node (ref "J13") (pin "16") (pinfunction "16_16") (pintype "passive"))
    )
    (net (code "30") (name "Net-(ASM-3-PadEN)") (class "Default")
      (node (ref "ASM-3") (pin "EN") (pinfunction "EN_EN") (pintype "passive"))
      (node (ref "J12") (pin "2") (pinfunction "2_2") (pintype "passive"))
    )
    (net (code "31") (name "Net-(ASM-3-PadVBAT)") (class "Default")
      (node (ref "ASM-3") (pin "VBAT") (pinfunction "VBAT_VBAT") (pintype "power_in"))
      (node (ref "J12") (pin "1") (pinfunction "1_1") (pintype "passive"))
    )
    (net (code "32") (name "Net-(ASM-3-~{RESET})") (class "Default")
      (node (ref "ASM-3") (pin "!RESET") (pinfunction "~{RESET}_!RESET") (pintype "input"))
      (node (ref "J13") (pin "1") (pinfunction "1_1") (pintype "passive"))
    )
    (net (code "33") (name "Net-(ASM-4-ACT)") (class "Default")
      (node (ref "ASM-4") (pin "13") (pinfunction "ACT_13") (pintype "output"))
      (node (ref "J16") (pin "13") (pinfunction "13_13") (pintype "passive"))
    )
    (net (code "34") (name "Net-(ASM-4-RX)") (class "Default")
      (node (ref "ASM-4") (pin "23") (pinfunction "RX_23") (pintype "input"))
      (node (ref "J15") (pin "6") (pinfunction "6_6") (pintype "passive"))
    )
    (net (code "35") (name "Net-(ASM-4-TX)") (class "Default")
      (node (ref "ASM-4") (pin "24") (pinfunction "TX_24") (pintype "output"))
      (node (ref "J15") (pin "5") (pinfunction "5_5") (pintype "passive"))
    )
    (net (code "36") (name "Net-(ASM-4-UART{slash}GPIO_SEL)") (class "Default")
      (node (ref "ASM-4") (pin "22") (pinfunction "UART/GPIO_SEL_22") (pintype "bidirectional"))
      (node (ref "J15") (pin "7") (pinfunction "7_7") (pintype "passive"))
    )
    (net (code "37") (name "Net-(ASM-4-USB{slash}VBUS)") (class "Default")
      (node (ref "ASM-4") (pin "26") (pinfunction "USB/VBUS_26") (pintype "power_in"))
      (node (ref "J15") (pin "3") (pinfunction "3_3") (pintype "passive"))
    )
    (net (code "38") (name "Net-(J1-Pad1)") (class "Default")
      (node (ref "J1") (pin "1") (pinfunction "1_1") (pintype "passive"))
      (node (ref "J2") (pin "1") (pinfunction "1_1") (pintype "bidirectional"))
      (node (ref "JP3") (pin "2") (pinfunction "2_2") (pintype "passive"))
    )
    (net (code "39") (name "Net-(J1-Pad2)") (class "Default")
      (node (ref "J1") (pin "2") (pinfunction "2_2") (pintype "passive"))
      (node (ref "J2") (pin "2") (pinfunction "2_2") (pintype "bidirectional"))
      (node (ref "JP4") (pin "2") (pinfunction "2_2") (pintype "passive"))
    )
    (net (code "40") (name "Net-(J1-Pad3)") (class "Default")
      (node (ref "J1") (pin "3") (pinfunction "3_3") (pintype "passive"))
      (node (ref "J2") (pin "3") (pinfunction "3_3") (pintype "bidirectional"))
      (node (ref "JP5") (pin "2") (pinfunction "2_2") (pintype "passive"))
    )
    (net (code "41") (name "Net-(J1-Pad4)") (class "Default")
      (node (ref "J1") (pin "4") (pinfunction "4_4") (pintype "passive"))
      (node (ref "J2") (pin "4") (pinfunction "4_4") (pintype "bidirectional"))
      (node (ref "JP6") (pin "2") (pinfunction "2_2") (pintype "passive"))
    )
    (net (code "42") (name "Net-(J1-Pad5)") (class "Default")
      (node (ref "J1") (pin "5") (pinfunction "5_5") (pintype "passive"))
      (node (ref "J2") (pin "5") (pinfunction "5_5") (pintype "bidirectional"))
      (node (ref "JP7") (pin "2") (pinfunction "2_2") (pintype "passive"))
    )
    (net (code "43") (name "Net-(J1-Pad6)") (class "Default")
      (node (ref "J1") (pin "6") (pinfunction "6_6") (pintype "passive"))
      (node (ref "J2") (pin "6") (pinfunction "6_6") (pintype "bidirectional"))
      (node (ref "JP8") (pin "2") (pinfunction "2_2") (pintype "passive"))
    )
    (net (code "44") (name "Net-(J4-P2)") (class "Default")
      (node (ref "J3") (pin "2") (pinfunction "2_2") (pintype "bidirectional"))
      (node (ref "J4") (pin "2") (pinfunction "P2_2") (pintype "passive"))
      (node (ref "Q1") (pin "P2") (pinfunction "D_P2") (pintype "passive"))
    )
    (net (code "45") (name "Net-(J14-P2)") (class "Default")
      (node (ref "D1") (pin "A") (pinfunction "A_A") (pintype "passive"))
      (node (ref "J14") (pin "2") (pinfunction "P2_2") (pintype "passive"))
      (node (ref "J19") (pin "2") (pinfunction "P2_2") (pintype "passive"))
      (node (ref "K1") (pin "COIL-2") (pinfunction "COIL-2_COIL-2") (pintype "bidirectional"))
      (node (ref "K2") (pin "COIL-2") (pinfunction "COIL-2_COIL-2") (pintype "bidirectional"))
      (node (ref "Q2") (pin "P2") (pinfunction "D_P2") (pintype "passive"))
      (node (ref "R10") (pin "P$1") (pinfunction "P1_P$1") (pintype "passive"))
    )
    (net (code "46") (name "Net-(LED1-C)") (class "Default")
      (node (ref "LED1") (pin "K") (pinfunction "C_K") (pintype "passive"))
      (node (ref "R10") (pin "P$2") (pinfunction "P2_P$2") (pintype "passive"))
    )
    (net (code "47") (name "Net-(Q1-G)") (class "Default")
      (node (ref "Q1") (pin "P1") (pinfunction "G_P1") (pintype "passive"))
      (node (ref "R1") (pin "P$1") (pinfunction "P1_P$1") (pintype "passive"))
      (node (ref "R4") (pin "P$2") (pinfunction "P2_P$2") (pintype "passive"))
    )
    (net (code "48") (name "Net-(Q2-G)") (class "Default")
      (node (ref "Q2") (pin "P1") (pinfunction "G_P1") (pintype "passive"))
      (node (ref "R8") (pin "P$2") (pinfunction "P2_P$2") (pintype "passive"))
      (node (ref "R9") (pin "P$1") (pinfunction "P1_P$1") (pintype "passive"))
    )
    (net (code "49") (name "Net-(R2-P2)") (class "Default")
      (node (ref "R2") (pin "P$2") (pinfunction "P2_P$2") (pintype "passive"))
      (node (ref "R3") (pin "P$1") (pinfunction "P1_P$1") (pintype "passive"))
      (node (ref "VRG-1") (pin "P1") (pinfunction "ADJ_P1") (pintype "power_in"))
    )
    (net (code "50") (name "Net-(R5-P1)") (class "Default")
      (node (ref "J20") (pin "3") (pinfunction "3_3") (pintype "bidirectional"))
      (node (ref "J20") (pin "4") (pinfunction "4_4") (pintype "bidirectional"))
      (node (ref "R5") (pin "P$1") (pinfunction "P1_P$1") (pintype "passive"))
    )
    (net (code "51") (name "Net-(R6-P2)") (class "Default")
      (node (ref "J21") (pin "3") (pinfunction "3_3") (pintype "bidirectional"))
      (node (ref "J21") (pin "4") (pinfunction "4_4") (pintype "bidirectional"))
      (node (ref "R6") (pin "P$2") (pinfunction "P2_P$2") (pintype "passive"))
    )
    (net (code "52") (name "Net-(R11-P2)") (class "Default")
      (node (ref "LED2") (pin "A") (pinfunction "A_A") (pintype "passive"))
      (node (ref "R11") (pin "P$2") (pinfunction "P2_P$2") (pintype "passive"))
    )
    (net (code "53") (name "Net-(VRG-2-R.C.)") (class "Default")
      (node (ref "J22") (pin "1") (pinfunction "1_1") (pintype "passive"))
      (node (ref "VRG-2") (pin "P$13") (pinfunction "R.C._P$13") (pintype "input"))
    )
    (net (code "54") (name "Net-(VRG-2-TRIM)") (class "Default")
      (node (ref "J22") (pin "2") (pinfunction "2_2") (pintype "passive"))
      (node (ref "VRG-2") (pin "P$12") (pinfunction "TRIM_P$12") (pintype "output"))
    )
    (net (code "55") (name "SFX-0") (class "Default")
      (node (ref "ASM-4") (pin "2") (pinfunction "0_2") (pintype "input"))
      (node (ref "J16") (pin "2") (pinfunction "2_2") (pintype "passive"))
      (node (ref "U1") (pin "22") (pinfunction "GPA1_22") (pintype "bidirectional"))
    )
    (net (code "56") (name "SFX-1") (class "Default")
      (node (ref "ASM-4") (pin "3") (pinfunction "1_3") (pintype "input"))
      (node (ref "J16") (pin "3") (pinfunction "3_3") (pintype "passive"))
      (node (ref "U1") (pin "23") (pinfunction "GPA2_23") (pintype "bidirectional"))
    )
    (net (code "57") (name "SFX-2") (class "Default")
      (node (ref "ASM-4") (pin "4") (pinfunction "2_4") (pintype "input"))
      (node (ref "J16") (pin "4") (pinfunction "4_4") (pintype "passive"))
      (node (ref "U1") (pin "24") (pinfunction "GPA3_24") (pintype "bidirectional"))
    )
    (net (code "58") (name "SFX-3") (class "Default")
      (node (ref "ASM-4") (pin "5") (pinfunction "3_5") (pintype "input"))
      (node (ref "J16") (pin "5") (pinfunction "5_5") (pintype "passive"))
      (node (ref "U1") (pin "25") (pinfunction "GPA4_25") (pintype "bidirectional"))
    )
    (net (code "59") (name "SFX-4") (class "Default")
      (node (ref "ASM-4") (pin "6") (pinfunction "4_6") (pintype "input"))
      (node (ref "J16") (pin "6") (pinfunction "6_6") (pintype "passive"))
      (node (ref "U1") (pin "26") (pinfunction "GPA5_26") (pintype "bidirectional"))
    )
    (net (code "60") (name "SFX-5") (class "Default")
      (node (ref "ASM-4") (pin "7") (pinfunction "5_7") (pintype "input"))
      (node (ref "J16") (pin "7") (pinfunction "7_7") (pintype "passive"))
      (node (ref "U1") (pin "27") (pinfunction "GPA6_27") (pintype "bidirectional"))
    )
    (net (code "61") (name "SFX-6") (class "Default")
      (node (ref "ASM-4") (pin "8") (pinfunction "6_8") (pintype "input"))
      (node (ref "J16") (pin "8") (pinfunction "8_8") (pintype "passive"))
      (node (ref "U1") (pin "28") (pinfunction "GPA7_28") (pintype "bidirectional"))
    )
    (net (code "62") (name "SFX-7") (class "Default")
      (node (ref "ASM-4") (pin "9") (pinfunction "7_9") (pintype "input"))
      (node (ref "J16") (pin "9") (pinfunction "9_9") (pintype "passive"))
      (node (ref "U1") (pin "8") (pinfunction "GPB7_8") (pintype "bidirectional"))
    )
    (net (code "63") (name "SFX-8") (class "Default")
      (node (ref "ASM-4") (pin "10") (pinfunction "8_10") (pintype "input"))
      (node (ref "J16") (pin "10") (pinfunction "10_10") (pintype "passive"))
      (node (ref "U1") (pin "7") (pinfunction "GPB6_7") (pintype "bidirectional"))
    )
    (net (code "64") (name "SFX-9") (class "Default")
      (node (ref "ASM-4") (pin "11") (pinfunction "9_11") (pintype "input"))
      (node (ref "J16") (pin "11") (pinfunction "11_11") (pintype "passive"))
      (node (ref "U1") (pin "6") (pinfunction "GPB5_6") (pintype "bidirectional"))
    )
    (net (code "65") (name "SFX-10") (class "Default")
      (node (ref "ASM-4") (pin "12") (pinfunction "10_12") (pintype "input"))
      (node (ref "J16") (pin "12") (pinfunction "12_12") (pintype "passive"))
      (node (ref "U1") (pin "5") (pinfunction "GPB4_5") (pintype "bidirectional"))
    )
    (net (code "66") (name "SFX-LOUT") (class "Default")
      (node (ref "ASM-1") (pin "4") (pinfunction "L+IN_4") (pintype "input"))
      (node (ref "ASM-4") (pin "16") (pinfunction "L+OUT_16") (pintype "output"))
      (node (ref "J15") (pin "13") (pinfunction "13_13") (pintype "passive"))
      (node (ref "J5") (pin "4") (pinfunction "4_4") (pintype "passive"))
    )
    (net (code "67") (name "SFX-ROUT") (class "Default")
      (node (ref "ASM-1") (pin "7") (pinfunction "R+IN_7") (pintype "input"))
      (node (ref "ASM-4") (pin "17") (pinfunction "R+OUT_17") (pintype "output"))
      (node (ref "J15") (pin "12") (pinfunction "12_12") (pintype "passive"))
      (node (ref "J5") (pin "1") (pinfunction "1_1") (pintype "passive"))
    )
    (net (code "68") (name "SFX-RST") (class "Default")
      (node (ref "ASM-4") (pin "1") (pinfunction "~{RESET}_1") (pintype "input"))
      (node (ref "J16") (pin "1") (pinfunction "1_1") (pintype "passive"))
      (node (ref "U1") (pin "21") (pinfunction "GPA0_21") (pintype "bidirectional"))
    )
    (net (code "69") (name "SFX-VOL-N") (class "Default")
      (node (ref "ASM-4") (pin "20") (pinfunction "VOL-_20") (pintype "input"))
      (node (ref "J15") (pin "9") (pinfunction "9_9") (pintype "passive"))
      (node (ref "U1") (pin "3") (pinfunction "GPB2_3") (pintype "bidirectional"))
    )
    (net (code "70") (name "SFX-VOL-P") (class "Default")
      (node (ref "ASM-4") (pin "21") (pinfunction "VOL+_21") (pintype "input"))
      (node (ref "J15") (pin "8") (pinfunction "8_8") (pintype "passive"))
      (node (ref "U1") (pin "4") (pinfunction "GPB3_4") (pintype "bidirectional"))
    )
    (net (code "71") (name "SPI-MISO") (class "Default")
      (node (ref "ASM-3") (pin "MISO") (pinfunction "MISO_MISO") (pintype "bidirectional"))
      (node (ref "J13") (pin "13") (pinfunction "13_13") (pintype "passive"))
    )
    (net (code "72") (name "SPI-MOSI") (class "Default")
      (node (ref "ASM-3") (pin "MOSI") (pinfunction "MOSI_MOSI") (pintype "bidirectional"))
      (node (ref "J13") (pin "12") (pinfunction "12_12") (pintype "passive"))
    )
    (net (code "73") (name "SPI-SCK") (class "Default")
      (node (ref "ASM-3") (pin "SCK") (pinfunction "SCK_SCK") (pintype "bidirectional"))
      (node (ref "J13") (pin "11") (pinfunction "11_11") (pintype "passive"))
    )
    (net (code "74") (name "unconnected-(ASM-1-GAIN1-Pad9)") (class "Default")
      (node (ref "ASM-1") (pin "9") (pinfunction "GAIN1_9") (pintype "passive"))
    )
    (net (code "75") (name "unconnected-(ASM-1-GAIN2-Pad8)") (class "Default")
      (node (ref "ASM-1") (pin "8") (pinfunction "GAIN2_8") (pintype "passive"))
    )
    (net (code "76") (name "unconnected-(ASM-1-L+OUT-Pad13)") (class "Default")
      (node (ref "ASM-1") (pin "13") (pinfunction "L+OUT_13") (pintype "output"))
    )
    (net (code "77") (name "unconnected-(ASM-1-L-OUT-Pad12)") (class "Default")
      (node (ref "ASM-1") (pin "12") (pinfunction "L-OUT_12") (pintype "output"))
    )
    (net (code "78") (name "unconnected-(ASM-1-R+OUT-Pad14)") (class "Default")
      (node (ref "ASM-1") (pin "14") (pinfunction "R+OUT_14") (pintype "output"))
    )
    (net (code "79") (name "unconnected-(ASM-1-R-OUT-Pad15)") (class "Default")
      (node (ref "ASM-1") (pin "15") (pinfunction "R-OUT_15") (pintype "output"))
    )
    (net (code "80") (name "unconnected-(ASM-4-CS-Pad19)") (class "Default")
      (node (ref "ASM-4") (pin "19") (pinfunction "CS_19") (pintype "no_connect"))
    )
    (net (code "81") (name "unconnected-(ASM-4-PB-Pad25)") (class "Default")
      (node (ref "ASM-4") (pin "25") (pinfunction "PB_25") (pintype "no_connect"))
    )
    (net (code "82") (name "unconnected-(J15-Pad4)") (class "Default")
      (node (ref "J15") (pin "4") (pinfunction "4_4") (pintype "passive"))
    )
    (net (code "83") (name "unconnected-(J15-Pad10)") (class "Default")
      (node (ref "J15") (pin "10") (pinfunction "10_10") (pintype "passive"))
    )
    (net (code "84") (name "unconnected-(K1-PadNC-2)") (class "Default")
      (node (ref "K1") (pin "NC-2") (pinfunction "NC-2_NC-2") (pintype "bidirectional"))
    )
    (net (code "85") (name "unconnected-(K2-PadNC-1)") (class "Default")
      (node (ref "K2") (pin "NC-1") (pinfunction "NC-1_NC-1") (pintype "bidirectional"))
    )
    (net (code "86") (name "unconnected-(MH1-P1-PadP$1)") (class "Default")
      (node (ref "MH1") (pin "P$1") (pinfunction "P1_P$1") (pintype "passive"))
    )
    (net (code "87") (name "unconnected-(MH2-P1-PadP$1)") (class "Default")
      (node (ref "MH2") (pin "P$1") (pinfunction "P1_P$1") (pintype "passive"))
    )
    (net (code "88") (name "unconnected-(MH3-P1-PadP$1)") (class "Default")
      (node (ref "MH3") (pin "P$1") (pinfunction "P1_P$1") (pintype "passive"))
    )
    (net (code "89") (name "unconnected-(MH4-P1-PadP$1)") (class "Default")
      (node (ref "MH4") (pin "P$1") (pinfunction "P1_P$1") (pintype "passive"))
    )
    (net (code "90") (name "unconnected-(THM-1-K-PadP$1)") (class "Default")
      (node (ref "THM-1") (pin "P$1") (pinfunction "K_P$1") (pintype "passive"))
    )
    (net (code "91") (name "unconnected-(U1-GPB0-Pad1)") (class "Default")
      (node (ref "U1") (pin "1") (pinfunction "GPB0_1") (pintype "bidirectional"))
    )
    (net (code "92") (name "unconnected-(U1-GPB1-Pad2)") (class "Default")
      (node (ref "U1") (pin "2") (pinfunction "GPB1_2") (pintype "bidirectional"))
    )
    (net (code "93") (name "unconnected-(U1-INTA-Pad20)") (class "Default")
      (node (ref "U1") (pin "20") (pinfunction "INTA_20") (pintype "output"))
    )
    (net (code "94") (name "unconnected-(U1-INTB-Pad19)") (class "Default")
      (node (ref "U1") (pin "19") (pinfunction "INTB_19") (pintype "output"))
    )
    (net (code "95") (name "unconnected-(U1-NC-Pad11)") (class "Default")
      (node (ref "U1") (pin "11") (pinfunction "NC_11") (pintype "no_connect"))
    )
    (net (code "96") (name "unconnected-(U1-NC-Pad14)") (class "Default")
      (node (ref "U1") (pin "14") (pinfunction "NC_14") (pintype "no_connect"))
    )
    (net (code "97") (name "unconnected-(VRG-2-NC-PadP$11)") (class "Default")
      (node (ref "VRG-2") (pin "P$11") (pinfunction "NC_P$11") (pintype "no_connect"))
    )
    (net (code "98") (name "~{AMP-SHDN}") (class "Default")
      (node (ref "ASM-1") (pin "3") (pinfunction "~{SHTDWN}_3") (pintype "input"))
      (node (ref "ASM-3") (pin "D10") (pinfunction "D10_D10") (pintype "bidirectional"))
      (node (ref "J12") (pin "7") (pinfunction "7_7") (pintype "passive"))
      (node (ref "J5") (pin "5") (pinfunction "5_5") (pintype "passive"))
      (node (ref "R7") (pin "P$2") (pinfunction "P2_P$2") (pintype "passive"))
    )
  )
)
